# justregulator.net
KiCad netlist of a schematic drawn in EAGLE
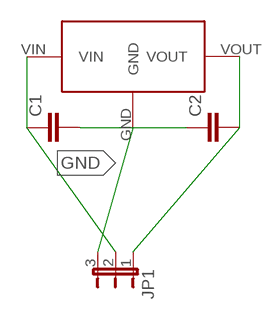
[diagram p0: schematic, sheet 1]

(export (version "E")
  (design (tool "Eeschema 10.0.6"))
  (components
    (comp (ref "C1")
      (value "C-EUC0603")
      (footprint "eagle-import:C0603")
      (libsource (lib "eagle-import") (part "C-EUC0603"))
    )
    (comp (ref "C2")
      (value "C-EUC0603")
      (footprint "eagle-import:C0603")
      (libsource (lib "eagle-import") (part "C-EUC0603"))
    )
    (comp (ref "JP1")
      (value "JP2E")
      (footprint "eagle-import:JP2")
      (libsource (lib "eagle-import") (part "JP2E"))
    )
    (comp (ref "U$1")
      (value "HT7333")
      (footprint "eagle-import:SOT89")
      (libsource (lib "eagle-import") (part "HT7333"))
    )
  )
  (nets
    (net (code "1") (name "GND") (class "Default")
      (node (ref "C1") (pin "2") (pinfunction "2_2") (pintype "passive"))
      (node (ref "C2") (pin "1") (pinfunction "1_1") (pintype "passive"))
      (node (ref "JP1") (pin "3") (pinfunction "3_3") (pintype "passive"))
      (node (ref "U$1") (pin "GND") (pinfunction "GND_GND") (pintype "bidirectional"))
    )
    (net (code "2") (name "Net-(C1-Pad1)") (class "Default")
      (node (ref "C1") (pin "1") (pinfunction "1_1") (pintype "passive"))
      (node (ref "JP1") (pin "2") (pinfunction "2_2") (pintype "passive"))
      (node (ref "U$1") (pin "VIN") (pinfunction "VIN_VIN") (pintype "bidirectional"))
    )
    (net (code "3") (name "Net-(C2-Pad2)") (class "Default")
      (node (ref "C2") (pin "2") (pinfunction "2_2") (pintype "passive"))
      (node (ref "JP1") (pin "1") (pinfunction "1_1") (pintype "passive"))
      (node (ref "U$1") (pin "VOUT") (pinfunction "VOUT_VOUT") (pintype "bidirectional"))
    )
  )
)
